# relay_dip_v02.net
KiCad netlist of a schematic drawn in EAGLE
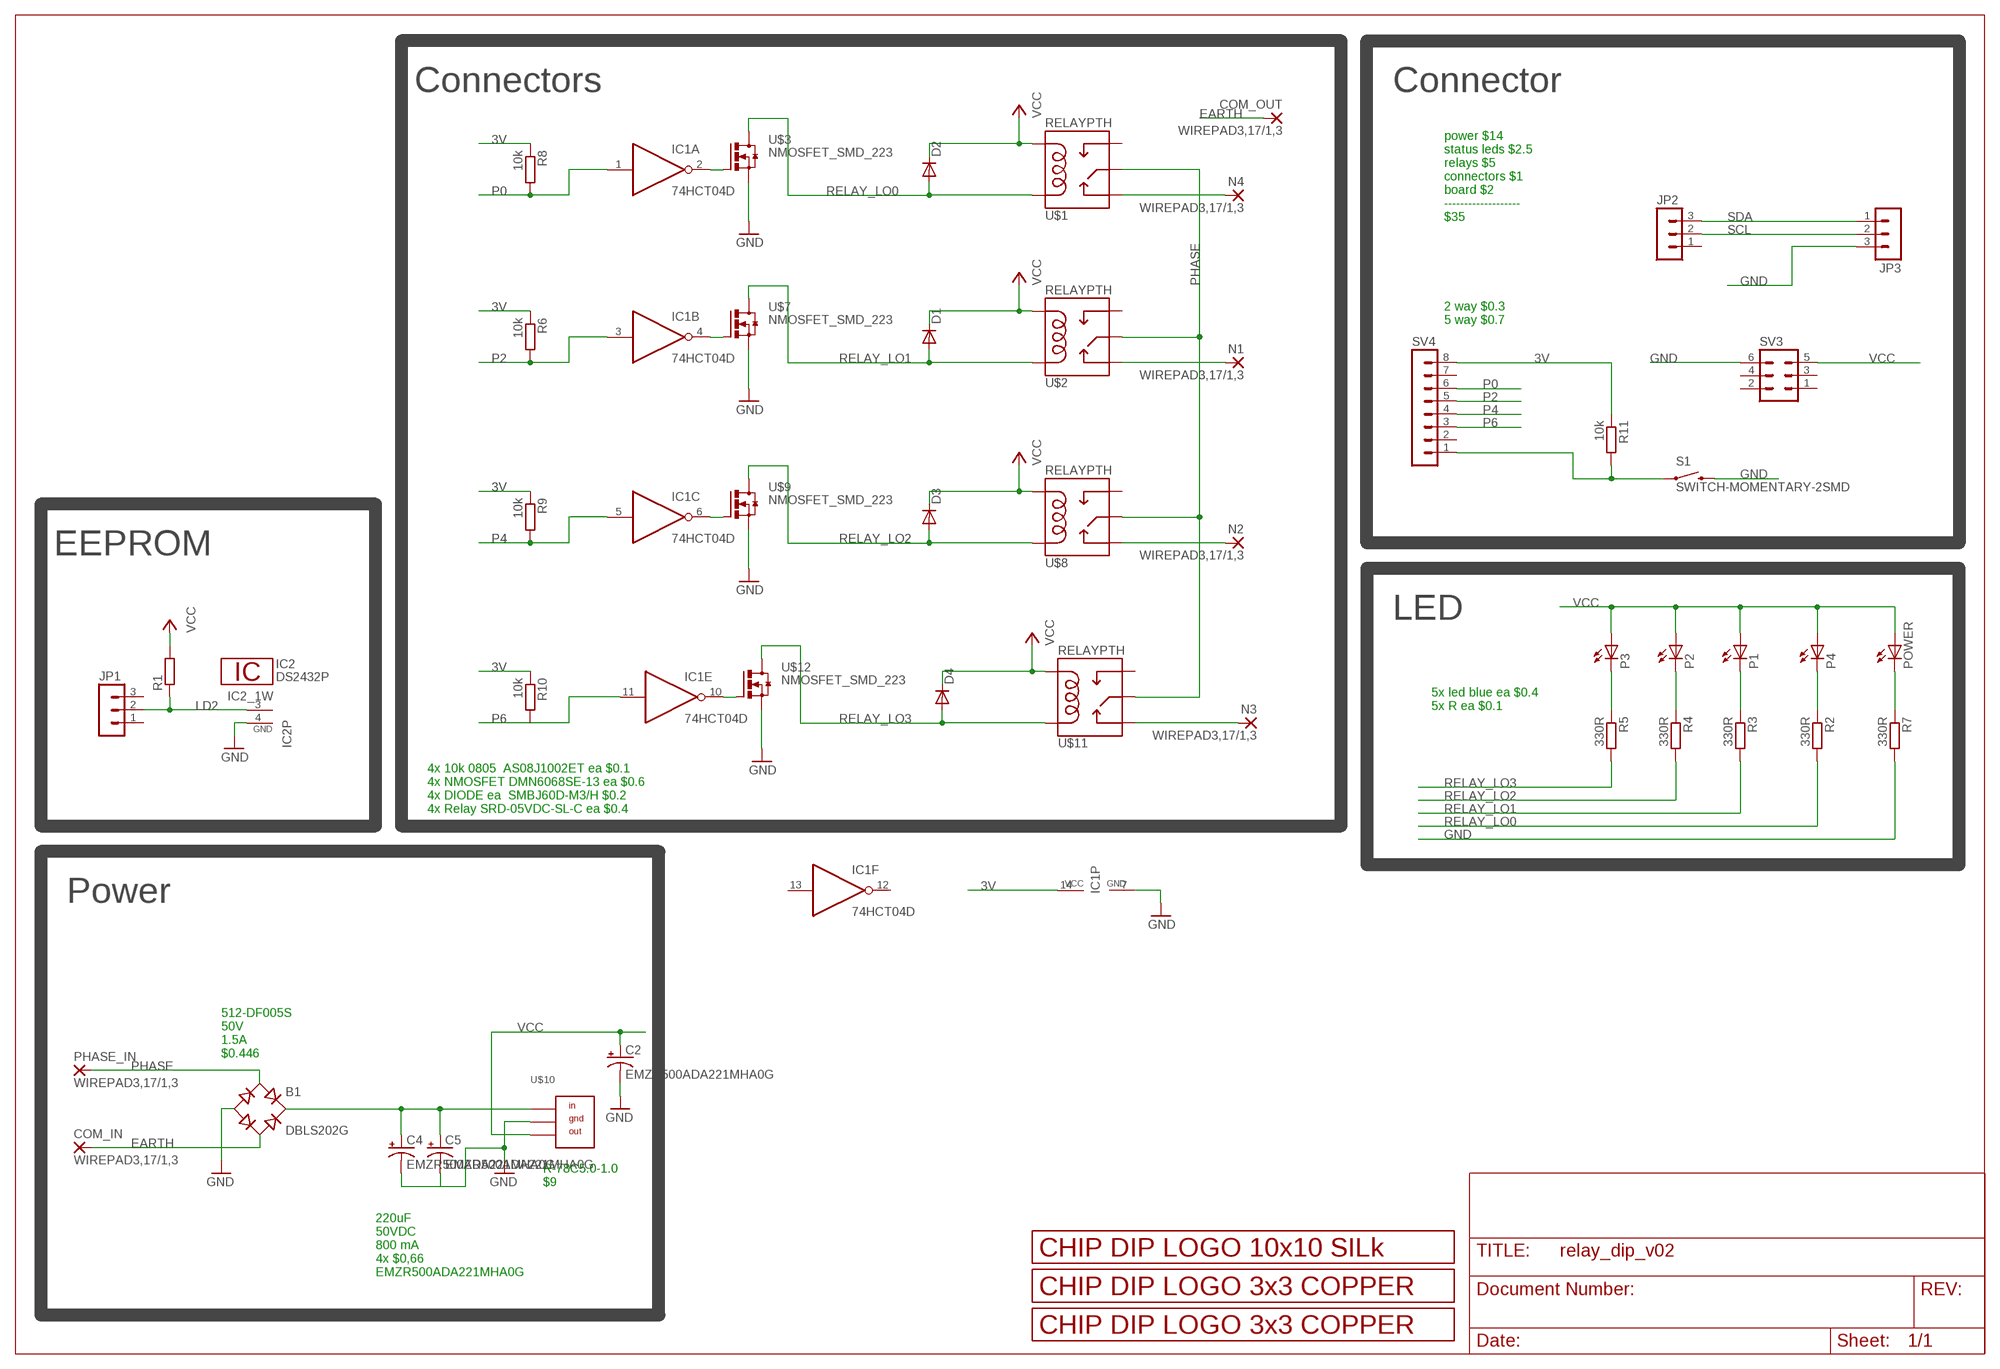
[diagram p0: schematic, sheet 1]

(export (version "E")
  (design (tool "Eeschema 10.0.6"))
  (components
    (comp (ref "B1")
      (value "DBLS202G")
      (footprint "eagle-import:DBS")
      (libsource (lib "eagle-import") (part "DB?GLS202"))
    )
    (comp (ref "C2")
      (value "EMZR500ADA221MHA0G")
      (footprint "eagle-import:150CLZ-0810")
      (libsource (lib "eagle-import") (part "CPOL-US150CLZ-0810"))
    )
    (comp (ref "C4")
      (value "EMZR500ADA221MHA0G")
      (footprint "eagle-import:150CLZ-0810")
      (libsource (lib "eagle-import") (part "CPOL-US150CLZ-0810"))
    )
    (comp (ref "C5")
      (value "EMZR500ADA221MHA0G")
      (footprint "eagle-import:150CLZ-0810")
      (libsource (lib "eagle-import") (part "CPOL-US150CLZ-0810"))
    )
    (comp (ref "COM_IN")
      (value "WIREPAD3,17/1,3")
      (footprint "eagle-import:3,17_1,3")
      (libsource (lib "eagle-import") (part "WIREPAD3,17/1,3"))
    )
    (comp (ref "COM_OUT")
      (value "WIREPAD3,17/1,3")
      (footprint "eagle-import:3,17_1,3")
      (libsource (lib "eagle-import") (part "WIREPAD3,17/1,3"))
    )
    (comp (ref "D1")
      (value "DIODE-SMB")
      (footprint "eagle-import:SMB")
      (libsource (lib "eagle-import") (part "DIODE-SMB"))
    )
    (comp (ref "D2")
      (value "DIODE-SMB")
      (footprint "eagle-import:SMB")
      (libsource (lib "eagle-import") (part "DIODE-SMB"))
    )
    (comp (ref "D3")
      (value "DIODE-SMB")
      (footprint "eagle-import:SMB")
      (libsource (lib "eagle-import") (part "DIODE-SMB"))
    )
    (comp (ref "D4")
      (value "DIODE-SMB")
      (footprint "eagle-import:SMB")
      (libsource (lib "eagle-import") (part "DIODE-SMB"))
    )
    (comp (ref "IC1")
      (value "74HCT04D")
      (footprint "eagle-import:SO14")
      (libsource (lib "eagle-import") (part "7404DHCT"))
    )
    (comp (ref "IC2")
      (value "DS2432P")
      (footprint "eagle-import:TSOC6")
      (libsource (lib "eagle-import") (part "DS2432P"))
    )
    (comp (ref "JP1")
      (value "MA03-1")
      (footprint "eagle-import:MA03-1")
      (libsource (lib "eagle-import") (part "MA03-1"))
    )
    (comp (ref "JP2")
      (value "MA03-1")
      (footprint "eagle-import:MA03-1")
      (libsource (lib "eagle-import") (part "MA03-1"))
    )
    (comp (ref "JP3")
      (value "MA03-1")
      (footprint "eagle-import:MA03-1")
      (libsource (lib "eagle-import") (part "MA03-1"))
    )
    (comp (ref "N1")
      (value "WIREPAD3,17/1,3")
      (footprint "eagle-import:3,17_1,3")
      (libsource (lib "eagle-import") (part "WIREPAD3,17/1,3"))
    )
    (comp (ref "N2")
      (value "WIREPAD3,17/1,3")
      (footprint "eagle-import:3,17_1,3")
      (libsource (lib "eagle-import") (part "WIREPAD3,17/1,3"))
    )
    (comp (ref "N3")
      (value "WIREPAD3,17/1,3")
      (footprint "eagle-import:3,17_1,3")
      (libsource (lib "eagle-import") (part "WIREPAD3,17/1,3"))
    )
    (comp (ref "N4")
      (value "WIREPAD3,17/1,3")
      (footprint "eagle-import:3,17_1,3")
      (libsource (lib "eagle-import") (part "WIREPAD3,17/1,3"))
    )
    (comp (ref "P1")
      (value "LEDCHIP-LED0805")
      (footprint "eagle-import:CHIP-LED0805")
      (libsource (lib "eagle-import") (part "LEDCHIP-LED0805"))
    )
    (comp (ref "P2")
      (value "LEDCHIP-LED0805")
      (footprint "eagle-import:CHIP-LED0805")
      (libsource (lib "eagle-import") (part "LEDCHIP-LED0805"))
    )
    (comp (ref "P3")
      (value "LEDCHIP-LED0805")
      (footprint "eagle-import:CHIP-LED0805")
      (libsource (lib "eagle-import") (part "LEDCHIP-LED0805"))
    )
    (comp (ref "P4")
      (value "LEDCHIP-LED0805")
      (footprint "eagle-import:CHIP-LED0805")
      (libsource (lib "eagle-import") (part "LEDCHIP-LED0805"))
    )
    (comp (ref "PHASE_IN")
      (value "WIREPAD3,17/1,3")
      (footprint "eagle-import:3,17_1,3")
      (libsource (lib "eagle-import") (part "WIREPAD3,17/1,3"))
    )
    (comp (ref "POWER")
      (value "LEDCHIP-LED0805")
      (footprint "eagle-import:CHIP-LED0805")
      (libsource (lib "eagle-import") (part "LEDCHIP-LED0805"))
    )
    (comp (ref "R1")
      (value "R-EU_R0805")
      (footprint "eagle-import:R0805")
      (libsource (lib "eagle-import") (part "R-EU_R0805"))
    )
    (comp (ref "R2")
      (value "330R")
      (footprint "eagle-import:R0805")
      (libsource (lib "eagle-import") (part "R-EU_R0805"))
    )
    (comp (ref "R3")
      (value "330R")
      (footprint "eagle-import:R0805")
      (libsource (lib "eagle-import") (part "R-EU_R0805"))
    )
    (comp (ref "R4")
      (value "330R")
      (footprint "eagle-import:R0805")
      (libsource (lib "eagle-import") (part "R-EU_R0805"))
    )
    (comp (ref "R5")
      (value "330R")
      (footprint "eagle-import:R0805")
      (libsource (lib "eagle-import") (part "R-EU_R0805"))
    )
    (comp (ref "R6")
      (value "10k")
      (footprint "eagle-import:R0805")
      (libsource (lib "eagle-import") (part "R-EU_R0805"))
    )
    (comp (ref "R7")
      (value "330R")
      (footprint "eagle-import:R0805")
      (libsource (lib "eagle-import") (part "R-EU_R0805"))
    )
    (comp (ref "R8")
      (value "10k")
      (footprint "eagle-import:R0805")
      (libsource (lib "eagle-import") (part "R-EU_R0805"))
    )
    (comp (ref "R9")
      (value "10k")
      (footprint "eagle-import:R0805")
      (libsource (lib "eagle-import") (part "R-EU_R0805"))
    )
    (comp (ref "R10")
      (value "10k")
      (footprint "eagle-import:R0805")
      (libsource (lib "eagle-import") (part "R-EU_R0805"))
    )
    (comp (ref "R11")
      (value "10k")
      (footprint "eagle-import:R0805")
      (libsource (lib "eagle-import") (part "R-EU_R0805"))
    )
    (comp (ref "S1")
      (value "SWITCH-MOMENTARY-2SMD")
      (footprint "eagle-import:TACTILE-SWITCH-SMD")
      (libsource (lib "eagle-import") (part "SWITCH-MOMENTARY-2SMD"))
    )
    (comp (ref "SV3")
      (value "MA03-2")
      (footprint "eagle-import:MA03-2")
      (libsource (lib "eagle-import") (part "MA03-2"))
    )
    (comp (ref "SV4")
      (value "MA08-1")
      (footprint "eagle-import:MA08-1")
      (libsource (lib "eagle-import") (part "MA08-1"))
    )
    (comp (ref "U$1")
      (value "RELAYPTH")
      (footprint "eagle-import:SRD-05VDC-SL-C")
      (libsource (lib "eagle-import") (part "RELAYPTH"))
    )
    (comp (ref "U$2")
      (value "RELAYPTH")
      (footprint "eagle-import:SRD-05VDC-SL-C")
      (libsource (lib "eagle-import") (part "RELAYPTH"))
    )
    (comp (ref "U$3")
      (value "NMOSFET_SMD_223")
      (footprint "eagle-import:SOT223")
      (libsource (lib "eagle-import") (part "NMOSFET_SMD_223"))
    )
    (comp (ref "U$4")
      (value "LOGO_3X3_COPPER")
      (footprint "eagle-import:LOGO_3X3_COPPER")
      (libsource (lib "eagle-import") (part "LOGO_3X3_COPPER"))
    )
    (comp (ref "U$5")
      (value "LOGO_10X10_SILK")
      (footprint "eagle-import:LOGO_10X10_SILK")
      (libsource (lib "eagle-import") (part "LOGO_10X10_SILK"))
    )
    (comp (ref "U$6")
      (value "LOGO_3X3_COPPER")
      (footprint "eagle-import:LOGO_3X3_COPPER")
      (libsource (lib "eagle-import") (part "LOGO_3X3_COPPER"))
    )
    (comp (ref "U$7")
      (value "NMOSFET_SMD_223")
      (footprint "eagle-import:SOT223")
      (libsource (lib "eagle-import") (part "NMOSFET_SMD_223"))
    )
    (comp (ref "U$8")
      (value "RELAYPTH")
      (footprint "eagle-import:SRD-05VDC-SL-C")
      (libsource (lib "eagle-import") (part "RELAYPTH"))
    )
    (comp (ref "U$9")
      (value "NMOSFET_SMD_223")
      (footprint "eagle-import:SOT223")
      (libsource (lib "eagle-import") (part "NMOSFET_SMD_223"))
    )
    (comp (ref "U$10")
      (value "R-7805-1.0")
      (footprint "eagle-import:SIP3")
      (libsource (lib "eagle-import") (part "R-7805-1.0"))
    )
    (comp (ref "U$11")
      (value "RELAYPTH")
      (footprint "eagle-import:SRD-05VDC-SL-C")
      (libsource (lib "eagle-import") (part "RELAYPTH"))
    )
    (comp (ref "U$12")
      (value "NMOSFET_SMD_223")
      (footprint "eagle-import:SOT223")
      (libsource (lib "eagle-import") (part "NMOSFET_SMD_223"))
    )
  )
  (nets
    (net (code "1") (name "/3V") (class "Default")
      (node (ref "IC1") (pin "14") (pinfunction "VCC_14") (pintype "power_in"))
      (node (ref "R10") (pin "1") (pinfunction "1_1") (pintype "passive"))
      (node (ref "R11") (pin "1") (pinfunction "1_1") (pintype "passive"))
      (node (ref "R6") (pin "1") (pinfunction "1_1") (pintype "passive"))
      (node (ref "R8") (pin "1") (pinfunction "1_1") (pintype "passive"))
      (node (ref "R9") (pin "1") (pinfunction "1_1") (pintype "passive"))
      (node (ref "SV4") (pin "8") (pinfunction "8_8") (pintype "passive"))
    )
    (net (code "2") (name "/EARTH") (class "Default")
      (node (ref "B1") (pin "AC2") (pinfunction "AC2_AC2") (pintype "passive"))
      (node (ref "COM_IN") (pin "1") (pinfunction "P_1") (pintype "passive"))
      (node (ref "COM_OUT") (pin "1") (pinfunction "P_1") (pintype "passive"))
    )
    (net (code "3") (name "/LD2") (class "Default")
      (node (ref "IC2") (pin "3") (pinfunction "1W_3") (pintype "power_in"))
      (node (ref "JP1") (pin "2") (pinfunction "2_2") (pintype "passive"))
      (node (ref "R1") (pin "1") (pinfunction "1_1") (pintype "passive"))
    )
    (net (code "4") (name "/P0") (class "Default")
      (node (ref "IC1") (pin "1") (pinfunction "I_1") (pintype "input"))
      (node (ref "R8") (pin "2") (pinfunction "2_2") (pintype "passive"))
      (node (ref "SV4") (pin "6") (pinfunction "6_6") (pintype "passive"))
    )
    (net (code "5") (name "/P2") (class "Default")
      (node (ref "IC1") (pin "3") (pinfunction "I_3") (pintype "input"))
      (node (ref "R6") (pin "2") (pinfunction "2_2") (pintype "passive"))
      (node (ref "SV4") (pin "5") (pinfunction "5_5") (pintype "passive"))
    )
    (net (code "6") (name "/P4") (class "Default")
      (node (ref "IC1") (pin "5") (pinfunction "I_5") (pintype "input"))
      (node (ref "R9") (pin "2") (pinfunction "2_2") (pintype "passive"))
      (node (ref "SV4") (pin "4") (pinfunction "4_4") (pintype "passive"))
    )
    (net (code "7") (name "/P6") (class "Default")
      (node (ref "IC1") (pin "11") (pinfunction "I_11") (pintype "input"))
      (node (ref "R10") (pin "2") (pinfunction "2_2") (pintype "passive"))
      (node (ref "SV4") (pin "3") (pinfunction "3_3") (pintype "passive"))
    )
    (net (code "8") (name "/PHASE") (class "Default")
      (node (ref "B1") (pin "AC1") (pinfunction "AC1_AC1") (pintype "passive"))
      (node (ref "PHASE_IN") (pin "1") (pinfunction "P_1") (pintype "passive"))
      (node (ref "U$1") (pin "SWCOMMON") (pinfunction "SWCOMMON_SWCOMMON") (pintype "bidirectional"))
      (node (ref "U$11") (pin "SWCOMMON") (pinfunction "SWCOMMON_SWCOMMON") (pintype "bidirectional"))
      (node (ref "U$2") (pin "SWCOMMON") (pinfunction "SWCOMMON_SWCOMMON") (pintype "bidirectional"))
      (node (ref "U$8") (pin "SWCOMMON") (pinfunction "SWCOMMON_SWCOMMON") (pintype "bidirectional"))
    )
    (net (code "9") (name "/RELAY_LO0") (class "Default")
      (node (ref "D2") (pin "A") (pinfunction "A_A") (pintype "passive"))
      (node (ref "R2") (pin "2") (pinfunction "2_2") (pintype "passive"))
      (node (ref "U$1") (pin "COIL1") (pinfunction "COIL1_COIL1") (pintype "bidirectional"))
      (node (ref "U$3") (pin "2") (pinfunction "D_2") (pintype "passive"))
      (node (ref "U$3") (pin "4") (pinfunction "D_4") (pintype "passive"))
    )
    (net (code "10") (name "/RELAY_LO1") (class "Default")
      (node (ref "D1") (pin "A") (pinfunction "A_A") (pintype "passive"))
      (node (ref "R3") (pin "2") (pinfunction "2_2") (pintype "passive"))
      (node (ref "U$2") (pin "COIL1") (pinfunction "COIL1_COIL1") (pintype "bidirectional"))
      (node (ref "U$7") (pin "2") (pinfunction "D_2") (pintype "passive"))
      (node (ref "U$7") (pin "4") (pinfunction "D_4") (pintype "passive"))
    )
    (net (code "11") (name "/RELAY_LO2") (class "Default")
      (node (ref "D3") (pin "A") (pinfunction "A_A") (pintype "passive"))
      (node (ref "R4") (pin "2") (pinfunction "2_2") (pintype "passive"))
      (node (ref "U$8") (pin "COIL1") (pinfunction "COIL1_COIL1") (pintype "bidirectional"))
      (node (ref "U$9") (pin "2") (pinfunction "D_2") (pintype "passive"))
      (node (ref "U$9") (pin "4") (pinfunction "D_4") (pintype "passive"))
    )
    (net (code "12") (name "/RELAY_LO3") (class "Default")
      (node (ref "D4") (pin "A") (pinfunction "A_A") (pintype "passive"))
      (node (ref "R5") (pin "2") (pinfunction "2_2") (pintype "passive"))
      (node (ref "U$11") (pin "COIL1") (pinfunction "COIL1_COIL1") (pintype "bidirectional"))
      (node (ref "U$12") (pin "2") (pinfunction "D_2") (pintype "passive"))
      (node (ref "U$12") (pin "4") (pinfunction "D_4") (pintype "passive"))
    )
    (net (code "13") (name "/SCL") (class "Default")
      (node (ref "JP2") (pin "2") (pinfunction "2_2") (pintype "passive"))
      (node (ref "JP3") (pin "2") (pinfunction "2_2") (pintype "passive"))
    )
    (net (code "14") (name "/SDA") (class "Default")
      (node (ref "JP2") (pin "3") (pinfunction "3_3") (pintype "passive"))
      (node (ref "JP3") (pin "1") (pinfunction "1_1") (pintype "passive"))
    )
    (net (code "15") (name "GND") (class "Default")
      (node (ref "B1") (pin "-") (pinfunction "-_-") (pintype "passive"))
      (node (ref "C2") (pin "-") (pinfunction "-_-") (pintype "passive"))
      (node (ref "C4") (pin "-") (pinfunction "-_-") (pintype "passive"))
      (node (ref "C5") (pin "-") (pinfunction "-_-") (pintype "passive"))
      (node (ref "IC1") (pin "7") (pinfunction "GND_7") (pintype "power_in"))
      (node (ref "IC2") (pin "4") (pinfunction "GND_4") (pintype "power_in"))
      (node (ref "JP3") (pin "3") (pinfunction "3_3") (pintype "passive"))
      (node (ref "R7") (pin "2") (pinfunction "2_2") (pintype "passive"))
      (node (ref "S1") (pin "3") (pinfunction "2_3") (pintype "passive"))
      (node (ref "SV3") (pin "6") (pinfunction "6_6") (pintype "passive"))
      (node (ref "U$10") (pin "GND") (pinfunction "GND_GND") (pintype "bidirectional"))
      (node (ref "U$12") (pin "3") (pinfunction "S_3") (pintype "passive"))
      (node (ref "U$3") (pin "3") (pinfunction "S_3") (pintype "passive"))
      (node (ref "U$7") (pin "3") (pinfunction "S_3") (pintype "passive"))
      (node (ref "U$9") (pin "3") (pinfunction "S_3") (pintype "passive"))
    )
    (net (code "16") (name "Net-(B1-Pad+)") (class "Default")
      (node (ref "B1") (pin "+") (pinfunction "+_+") (pintype "passive"))
      (node (ref "C4") (pin "+") (pinfunction "+_+") (pintype "passive"))
      (node (ref "C5") (pin "+") (pinfunction "+_+") (pintype "passive"))
      (node (ref "U$10") (pin "IN") (pinfunction "IN_IN") (pintype "bidirectional"))
    )
    (net (code "17") (name "Net-(IC1A-O)") (class "Default")
      (node (ref "IC1") (pin "2") (pinfunction "O_2") (pintype "output"))
      (node (ref "U$3") (pin "1") (pinfunction "G_1") (pintype "passive"))
    )
    (net (code "18") (name "Net-(IC1B-O)") (class "Default")
      (node (ref "IC1") (pin "4") (pinfunction "O_4") (pintype "output"))
      (node (ref "U$7") (pin "1") (pinfunction "G_1") (pintype "passive"))
    )
    (net (code "19") (name "Net-(IC1C-O)") (class "Default")
      (node (ref "IC1") (pin "6") (pinfunction "O_6") (pintype "output"))
      (node (ref "U$9") (pin "1") (pinfunction "G_1") (pintype "passive"))
    )
    (net (code "20") (name "Net-(IC1E-O)") (class "Default")
      (node (ref "IC1") (pin "10") (pinfunction "O_10") (pintype "output"))
      (node (ref "U$12") (pin "1") (pinfunction "G_1") (pintype "passive"))
    )
    (net (code "21") (name "Net-(N1-P)") (class "Default")
      (node (ref "N1") (pin "1") (pinfunction "P_1") (pintype "passive"))
      (node (ref "U$2") (pin "SWCLOSED") (pinfunction "SWCLOSE_SWCLOSED") (pintype "bidirectional"))
    )
    (net (code "22") (name "Net-(N2-P)") (class "Default")
      (node (ref "N2") (pin "1") (pinfunction "P_1") (pintype "passive"))
      (node (ref "U$8") (pin "SWCLOSED") (pinfunction "SWCLOSE_SWCLOSED") (pintype "bidirectional"))
    )
    (net (code "23") (name "Net-(N3-P)") (class "Default")
      (node (ref "N3") (pin "1") (pinfunction "P_1") (pintype "passive"))
      (node (ref "U$11") (pin "SWCLOSED") (pinfunction "SWCLOSE_SWCLOSED") (pintype "bidirectional"))
    )
    (net (code "24") (name "Net-(N4-P)") (class "Default")
      (node (ref "N4") (pin "1") (pinfunction "P_1") (pintype "passive"))
      (node (ref "U$1") (pin "SWCLOSED") (pinfunction "SWCLOSE_SWCLOSED") (pintype "bidirectional"))
    )
    (net (code "25") (name "Net-(P1-PadC)") (class "Default")
      (node (ref "P1") (pin "C") (pinfunction "C_C") (pintype "passive"))
      (node (ref "R3") (pin "1") (pinfunction "1_1") (pintype "passive"))
    )
    (net (code "26") (name "Net-(P2-PadC)") (class "Default")
      (node (ref "P2") (pin "C") (pinfunction "C_C") (pintype "passive"))
      (node (ref "R4") (pin "1") (pinfunction "1_1") (pintype "passive"))
    )
    (net (code "27") (name "Net-(P3-PadC)") (class "Default")
      (node (ref "P3") (pin "C") (pinfunction "C_C") (pintype "passive"))
      (node (ref "R5") (pin "1") (pinfunction "1_1") (pintype "passive"))
    )
    (net (code "28") (name "Net-(P4-PadC)") (class "Default")
      (node (ref "P4") (pin "C") (pinfunction "C_C") (pintype "passive"))
      (node (ref "R2") (pin "1") (pinfunction "1_1") (pintype "passive"))
    )
    (net (code "29") (name "Net-(POWER-PadC)") (class "Default")
      (node (ref "POWER") (pin "C") (pinfunction "C_C") (pintype "passive"))
      (node (ref "R7") (pin "1") (pinfunction "1_1") (pintype "passive"))
    )
    (net (code "30") (name "Net-(R11-Pad2)") (class "Default")
      (node (ref "R11") (pin "2") (pinfunction "2_2") (pintype "passive"))
      (node (ref "S1") (pin "1") (pinfunction "1_1") (pintype "passive"))
      (node (ref "SV4") (pin "1") (pinfunction "1_1") (pintype "passive"))
    )
    (net (code "31") (name "VCC") (class "Default")
      (node (ref "C2") (pin "+") (pinfunction "+_+") (pintype "passive"))
      (node (ref "D1") (pin "C") (pinfunction "C_C") (pintype "passive"))
      (node (ref "D2") (pin "C") (pinfunction "C_C") (pintype "passive"))
      (node (ref "D3") (pin "C") (pinfunction "C_C") (pintype "passive"))
      (node (ref "D4") (pin "C") (pinfunction "C_C") (pintype "passive"))
      (node (ref "P1") (pin "A") (pinfunction "A_A") (pintype "passive"))
      (node (ref "P2") (pin "A") (pinfunction "A_A") (pintype "passive"))
      (node (ref "P3") (pin "A") (pinfunction "A_A") (pintype "passive"))
      (node (ref "P4") (pin "A") (pinfunction "A_A") (pintype "passive"))
      (node (ref "POWER") (pin "A") (pinfunction "A_A") (pintype "passive"))
      (node (ref "R1") (pin "2") (pinfunction "2_2") (pintype "passive"))
      (node (ref "SV3") (pin "5") (pinfunction "5_5") (pintype "passive"))
      (node (ref "U$1") (pin "COIL0") (pinfunction "COIL0_COIL0") (pintype "bidirectional"))
      (node (ref "U$10") (pin "OUT") (pinfunction "OUT_OUT") (pintype "bidirectional"))
      (node (ref "U$11") (pin "COIL0") (pinfunction "COIL0_COIL0") (pintype "bidirectional"))
      (node (ref "U$2") (pin "COIL0") (pinfunction "COIL0_COIL0") (pintype "bidirectional"))
      (node (ref "U$8") (pin "COIL0") (pinfunction "COIL0_COIL0") (pintype "bidirectional"))
    )
    (net (code "32") (name "unconnected-(IC1F-I-Pad13)") (class "Default")
      (node (ref "IC1") (pin "13") (pinfunction "I_13") (pintype "input"))
    )
    (net (code "33") (name "unconnected-(IC1F-O-Pad12)") (class "Default")
      (node (ref "IC1") (pin "12") (pinfunction "O_12") (pintype "output"))
    )
    (net (code "34") (name "unconnected-(JP1-Pad1)") (class "Default")
      (node (ref "JP1") (pin "1") (pinfunction "1_1") (pintype "passive"))
    )
    (net (code "35") (name "unconnected-(JP1-Pad3)") (class "Default")
      (node (ref "JP1") (pin "3") (pinfunction "3_3") (pintype "passive"))
    )
    (net (code "36") (name "unconnected-(JP2-Pad1)") (class "Default")
      (node (ref "JP2") (pin "1") (pinfunction "1_1") (pintype "passive"))
    )
    (net (code "37") (name "unconnected-(SV3-Pad1)") (class "Default")
      (node (ref "SV3") (pin "1") (pinfunction "1_1") (pintype "passive"))
    )
    (net (code "38") (name "unconnected-(SV3-Pad2)") (class "Default")
      (node (ref "SV3") (pin "2") (pinfunction "2_2") (pintype "passive"))
    )
    (net (code "39") (name "unconnected-(SV3-Pad3)") (class "Default")
      (node (ref "SV3") (pin "3") (pinfunction "3_3") (pintype "passive"))
    )
    (net (code "40") (name "unconnected-(SV3-Pad4)") (class "Default")
      (node (ref "SV3") (pin "4") (pinfunction "4_4") (pintype "passive"))
    )
    (net (code "41") (name "unconnected-(SV4-Pad2)") (class "Default")
      (node (ref "SV4") (pin "2") (pinfunction "2_2") (pintype "passive"))
    )
    (net (code "42") (name "unconnected-(SV4-Pad7)") (class "Default")
      (node (ref "SV4") (pin "7") (pinfunction "7_7") (pintype "passive"))
    )
    (net (code "43") (name "unconnected-(U$1-PadSWOPEN)") (class "Default")
      (node (ref "U$1") (pin "SWOPEN") (pinfunction "SWOPEN_SWOPEN") (pintype "bidirectional"))
    )
    (net (code "44") (name "unconnected-(U$2-PadSWOPEN)") (class "Default")
      (node (ref "U$2") (pin "SWOPEN") (pinfunction "SWOPEN_SWOPEN") (pintype "bidirectional"))
    )
    (net (code "45") (name "unconnected-(U$8-PadSWOPEN)") (class "Default")
      (node (ref "U$8") (pin "SWOPEN") (pinfunction "SWOPEN_SWOPEN") (pintype "bidirectional"))
    )
    (net (code "46") (name "unconnected-(U$11-PadSWOPEN)") (class "Default")
      (node (ref "U$11") (pin "SWOPEN") (pinfunction "SWOPEN_SWOPEN") (pintype "bidirectional"))
    )
  )
)
